# 48V-5V_Buck.net
KiCad netlist of a schematic drawn in Altium Designer
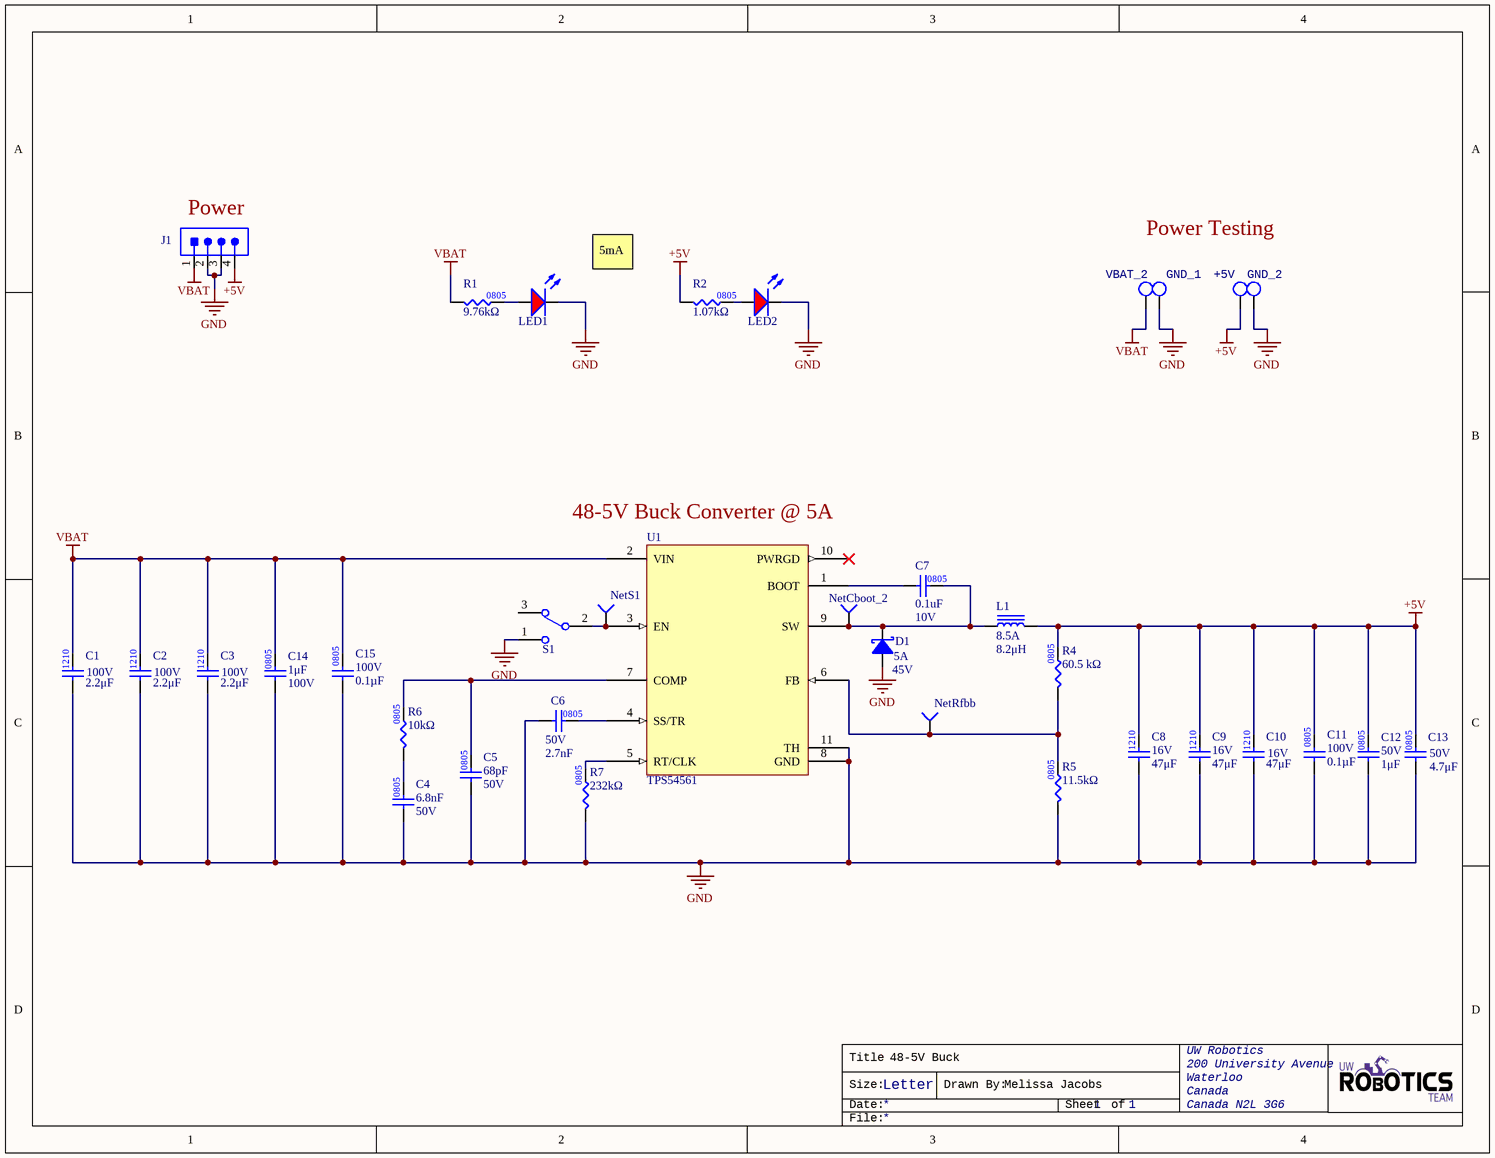
[diagram p0: 48V-5V Buck.SchDoc]

(export (version "E")
  (design (tool "Eeschema 10.0.6"))
  (components
    (comp (ref "+5V")
      (value "TESTPOINT_LOOP")
      (footprint "TESTPOINT_LOOP")
      (description "TESTPOINT THRUHOLE")
      (libsource (lib "UWRT_Schematic_Library_2020") (part "TESTPOINT_LOOP"))
    )
    (comp (ref "C1")
      (value "2.2μF")
      (footprint "CAPC3225X270N")
      (description "CAP CER 2.2UF 100V X7R 1210")
      (fields (field (name "VOLTAGE RATING") "100V") (field (name "Comment") "CAP_2.2uF_100V_1210_1"))
      (libsource (lib "UWRT_Schematic_Library_2020") (part "CAP_2.2uF_100V_1210_1"))
    )
    (comp (ref "C2")
      (value "2.2μF")
      (footprint "CAPC3225X270N")
      (description "CAP CER 2.2UF 100V X7R 1210")
      (fields (field (name "VOLTAGE RATING") "100V") (field (name "Comment") "CAP_2.2uF_100V_1210_1"))
      (libsource (lib "UWRT_Schematic_Library_2020") (part "CAP_2.2uF_100V_1210_1"))
    )
    (comp (ref "C3")
      (value "2.2μF")
      (footprint "CAPC3225X270N")
      (description "CAP CER 2.2UF 100V X7R 1210")
      (fields (field (name "VOLTAGE RATING") "100V") (field (name "Comment") "CAP_2.2uF_100V_1210_1"))
      (libsource (lib "UWRT_Schematic_Library_2020") (part "CAP_2.2uF_100V_1210_1"))
    )
    (comp (ref "C4")
      (value "6.8nF")
      (footprint "CAP0805")
      (description "CAP CER 6800PF 50V C0G/NP0 0805")
      (fields (field (name "VOLTAGE RATING") "50V") (field (name "Comment") "CAP_6.8nF_100V_0805"))
      (libsource (lib "UWRT_Schematic_Library_2020") (part "CAP_6.8nF_100V_0805"))
    )
    (comp (ref "C5")
      (value "68pF")
      (footprint "CAP0805")
      (description "CAP CER 68PF 50V C0G/NP0 0805")
      (fields (field (name "VOLTAGE RATING") "50V") (field (name "Comment") "CAP_68pF_50V_0805"))
      (libsource (lib "UWRT_Schematic_Library_2020") (part "CAP_68pF_50V_0805"))
    )
    (comp (ref "C6")
      (value "2.7nF")
      (footprint "CAP0805")
      (description "CAP CER 2700PF 50V C0G 0805")
      (fields (field (name "VOLTAGE RATING") "50V") (field (name "Comment") "CAP_2.7nF_50V_0805"))
      (libsource (lib "UWRT_Schematic_Library_2020") (part "CAP_2.7nF_50V_0805"))
    )
    (comp (ref "C7")
      (value "0.1uF")
      (footprint "CAP0805")
      (description "CAP CER 0.1uF 10V 0805")
      (fields (field (name "VOLTAGE RATING") "10V") (field (name "Comment") "CAP_0.1uF_10V_0805"))
      (libsource (lib "UWRT_Schematic_Library_2020") (part "CAP_0.1uF_10V_0805"))
    )
    (comp (ref "C8")
      (value "47μF")
      (footprint "CAPC3225X270N")
      (description "CAP CER 47uF 16V X5R 1210")
      (fields (field (name "VOLTAGE RATING") "16V") (field (name "Comment") "CAP_47uF_16V_1210"))
      (libsource (lib "UWRT_Schematic_Library_2020") (part "CAP_47uF_16V_1210"))
    )
    (comp (ref "C9")
      (value "47μF")
      (footprint "CAPC3225X270N")
      (description "CAP CER 47uF 16V X5R 1210")
      (fields (field (name "VOLTAGE RATING") "16V") (field (name "Comment") "CAP_47uF_16V_1210"))
      (libsource (lib "UWRT_Schematic_Library_2020") (part "CAP_47uF_16V_1210"))
    )
    (comp (ref "C10")
      (value "47μF")
      (footprint "CAPC3225X270N")
      (description "CAP CER 47uF 16V X5R 1210")
      (fields (field (name "VOLTAGE RATING") "16V") (field (name "Comment") "CAP_47uF_16V_1210"))
      (libsource (lib "UWRT_Schematic_Library_2020") (part "CAP_47uF_16V_1210"))
    )
    (comp (ref "C11")
      (value "0.1µF")
      (footprint "CAP0805")
      (description "CAP CER 0.1UF 100V X7R 0805")
      (fields (field (name "VOLTAGE RATING") "100V") (field (name "Comment") "CAP_0.1uF_100V_0805"))
      (libsource (lib "UWRT_Schematic_Library_2020") (part "CAP_0.1uF_100V_0805"))
    )
    (comp (ref "C12")
      (value "1μF")
      (footprint "CAP0805")
      (description "CAP CER 1UF 50V X7R 0805")
      (fields
        (field (name "LCSC PART #") "C28323")
        (field (name "VOLTAGE RATING") "50V")
        (field (name "Comment") "CAP_1uF_50V_0805")
      )
      (libsource (lib "UWRT_Schematic_Library_2020") (part "CAP_1uF_50V_0805"))
    )
    (comp (ref "C13")
      (value "4.7μF")
      (footprint "CAP0805")
      (description "CAP CER 4.7UF 50V X5R 0805")
      (fields
        (field (name "LCSC PART #") "C1779")
        (field (name "VOLTAGE RATING") "50V")
        (field (name "Comment") "CAP_4.7uF_50V_0805")
      )
      (libsource (lib "UWRT_Schematic_Library_2020") (part "CAP_4.7uF_50V_0805"))
    )
    (comp (ref "C14")
      (value "1μF")
      (footprint "CAP0805")
      (description "CAP CER 1UF 100V X7S 0805")
      (fields (field (name "VOLTAGE RATING") "100V") (field (name "Comment") "CAP_1uF_100V_0805"))
      (libsource (lib "UWRT_Schematic_Library_2020") (part "CAP_1uF_100V_0805"))
    )
    (comp (ref "C15")
      (value "0.1µF")
      (footprint "CAP0805")
      (description "CAP CER 0.1UF 100V X7R 0805")
      (fields (field (name "VOLTAGE RATING") "100V") (field (name "Comment") "CAP_0.1uF_100V_0805"))
      (libsource (lib "UWRT_Schematic_Library_2020") (part "CAP_0.1uF_100V_0805"))
    )
    (comp (ref "D1")
      (value "DIO_SCHOTTKY_100V_5.5A")
      (footprint "DIO_SCHOTTKY_45V_5A_vF480mV")
      (description "DIODE SCHOTTKY 45V 5A DO214AA")
      (fields (field (name "AVERAGE RECTIFIED CURRENT") "5A") (field (name "VR (MAX)") "45V"))
      (libsource (lib "UWRT_Schematic_Library_2020") (part "DIO_SCHOTTKY_45V_5A"))
    )
    (comp (ref "GND_1")
      (value "TESTPOINT_LOOP")
      (footprint "TESTPOINT_LOOP")
      (description "TESTPOINT THRUHOLE")
      (libsource (lib "UWRT_Schematic_Library_2020") (part "TESTPOINT_LOOP"))
    )
    (comp (ref "GND_2")
      (value "TESTPOINT_LOOP")
      (footprint "TESTPOINT_LOOP")
      (description "TESTPOINT THRUHOLE")
      (libsource (lib "UWRT_Schematic_Library_2020") (part "TESTPOINT_LOOP"))
    )
    (comp (ref "J1")
      (value "CON_2POS_SCREW_TERM")
      (footprint "MPT-04-01-01-L-RA-SD")
      (description "CONN HDR 4POS 5MM R/A SLDR")
      (libsource (lib "UWRT_Schematic_Library_2020") (part "CON_4POS_POWERBLADE_MALE"))
    )
    (comp (ref "L1")
      (value "8.2μH")
      (footprint "IND_8.2uH_8.5A")
      (description "FIXED IND 8.2UH 8.5A 28 MOHM SMD")
      (fields (field (name "CURRENT RATING") "8.5A") (field (name "Comment") "IND_8.2uH_8.5A"))
      (libsource (lib "UWRT_Schematic_Library_2020") (part "IND_8.2uH_8.5A"))
    )
    (comp (ref "LED1")
      (value "LED_RED")
      (footprint "LED_0805_RED")
      (description "LED RED DIFFUSED 0805 SMD")
      (libsource (lib "UWRT_Schematic_Library_2020") (part "LED_RED"))
    )
    (comp (ref "LED2")
      (value "LED_RED")
      (footprint "LED_0805_RED")
      (description "LED RED DIFFUSED 0805 SMD")
      (libsource (lib "UWRT_Schematic_Library_2020") (part "LED_RED"))
    )
    (comp (ref "NetCboot_2")
      (value "TESTPOINT_1MM_CIRCLE")
      (footprint "TESTPOINT_CIRCLE_1MM")
      (description "TESTPOINT 1MM CIRCLE")
      (libsource (lib "UWRT_Schematic_Library_2020") (part "TESTPOINT_1MM_CIRCLE"))
    )
    (comp (ref "NetRfbb")
      (value "TESTPOINT_1MM_CIRCLE")
      (footprint "TESTPOINT_CIRCLE_1MM")
      (description "TESTPOINT 1MM CIRCLE")
      (libsource (lib "UWRT_Schematic_Library_2020") (part "TESTPOINT_1MM_CIRCLE"))
    )
    (comp (ref "NetS1")
      (value "TESTPOINT_1MM_CIRCLE")
      (footprint "TESTPOINT_CIRCLE_1MM")
      (description "TESTPOINT 1MM CIRCLE")
      (libsource (lib "UWRT_Schematic_Library_2020") (part "TESTPOINT_1MM_CIRCLE"))
    )
    (comp (ref "R1")
      (value "9.76kΩ")
      (footprint "RES0805")
      (description "RES 9.76K OHM 1% 1/8W 0805")
      (fields (field (name "Comment") "RES_9.76kΩ_0805_1%"))
      (libsource (lib "UWRT_Schematic_Library_2020") (part "RES_9.76kΩ_0805_1%"))
    )
    (comp (ref "R2")
      (value "1.07kΩ")
      (footprint "RES0805")
      (description "RES 1K OHM 1% 1/8W 0805")
      (fields (field (name "Comment") "RES_1kΩ_0805_1%"))
      (libsource (lib "UWRT_Schematic_Library_2020") (part "RES_1kΩ_0805_1%"))
    )
    (comp (ref "R4")
      (value "60.5 kΩ")
      (footprint "RES0805")
      (description "RES 60.5 kOHM 63 mW 0805")
      (fields (field (name "Comment") "RES_60.4kΩ_0805_1%"))
      (libsource (lib "UWRT_Schematic_Library_2020") (part "RES_60.4kΩ_0805_1%"))
    )
    (comp (ref "R5")
      (value "11.5kΩ")
      (footprint "RES0805")
      (description "RES 11.5K OHM 0.1% 1/10W 0805")
      (fields (field (name "Comment") "RES_11.5kΩ_0805_0.1%"))
      (libsource (lib "UWRT_Schematic_Library_2020") (part "RES_11.5kΩ_0805_0.1%"))
    )
    (comp (ref "R6")
      (value "10kΩ")
      (footprint "RES0805")
      (description "RES 10K OHM 5% 1/8W 0805")
      (fields (field (name "LCSC PART #") "C17414") (field (name "Comment") "RES_10kΩ_0805_5%"))
      (libsource (lib "UWRT_Schematic_Library_2020") (part "RES_10kΩ_0805_5%"))
    )
    (comp (ref "R7")
      (value "232kΩ")
      (footprint "RES0805")
      (description "RES 232K OHM 1% 1/8W 0805")
      (fields (field (name "LCSC PART #") "0") (field (name "Comment") "RES_232kΩ_0805_1%"))
      (libsource (lib "UWRT_Schematic_Library_2020") (part "RES_232kΩ_0805_1%"))
    )
    (comp (ref "S1")
      (value "SW_SLIDE_TOGGLE")
      (footprint "UWRT_Footprint_Library_2020:SW_SLIDE_TOGGLE")
      (description "SWITCH SLIDE SPDT 200MA 30V")
      (libsource (lib "UWRT_Schematic_Library_2020") (part "SW_SLIDE_TOGGLE"))
    )
    (comp (ref "U1")
      (value "TPS54561")
      (footprint "BUCK_TPS54561DPRR")
      (description "Buck Switching Regulator IC Positive Adjustable 0.8V 1 Output 5A 10-WDFN Exposed Pad")
      (libsource (lib "UWRT_Schematic_Library_2020") (part "TPS54561"))
    )
    (comp (ref "VBAT_2")
      (value "TESTPOINT_LOOP")
      (footprint "TESTPOINT_LOOP")
      (description "TESTPOINT THRUHOLE")
      (libsource (lib "UWRT_Schematic_Library_2020") (part "TESTPOINT_LOOP"))
    )
  )
  (nets
    (net (code "1") (name "+5V") (class "Default")
      (node (ref "+5V") (pin "1") (pintype "passive"))
      (node (ref "C10") (pin "2") (pinfunction "2_2") (pintype "passive"))
      (node (ref "C11") (pin "2") (pinfunction "2_2") (pintype "passive"))
      (node (ref "C12") (pin "2") (pinfunction "2_2") (pintype "passive"))
      (node (ref "C13") (pin "2") (pinfunction "2_2") (pintype "passive"))
      (node (ref "C8") (pin "2") (pinfunction "2_2") (pintype "passive"))
      (node (ref "C9") (pin "2") (pinfunction "2_2") (pintype "passive"))
      (node (ref "J1") (pin "4") (pinfunction "2_4") (pintype "passive"))
      (node (ref "L1") (pin "2") (pinfunction "2_2") (pintype "passive"))
      (node (ref "R2") (pin "1") (pinfunction "1_1") (pintype "passive"))
      (node (ref "R4") (pin "2") (pinfunction "2_2") (pintype "passive"))
    )
    (net (code "2") (name "GND") (class "Default")
      (node (ref "C1") (pin "1") (pinfunction "1_1") (pintype "passive"))
      (node (ref "C10") (pin "1") (pinfunction "1_1") (pintype "passive"))
      (node (ref "C11") (pin "1") (pinfunction "1_1") (pintype "passive"))
      (node (ref "C12") (pin "1") (pinfunction "1_1") (pintype "passive"))
      (node (ref "C13") (pin "1") (pinfunction "1_1") (pintype "passive"))
      (node (ref "C14") (pin "1") (pinfunction "1_1") (pintype "passive"))
      (node (ref "C15") (pin "1") (pinfunction "1_1") (pintype "passive"))
      (node (ref "C2") (pin "1") (pinfunction "1_1") (pintype "passive"))
      (node (ref "C3") (pin "1") (pinfunction "1_1") (pintype "passive"))
      (node (ref "C4") (pin "1") (pinfunction "1_1") (pintype "passive"))
      (node (ref "C5") (pin "1") (pinfunction "1_1") (pintype "passive"))
      (node (ref "C6") (pin "1") (pinfunction "1_1") (pintype "passive"))
      (node (ref "C8") (pin "1") (pinfunction "1_1") (pintype "passive"))
      (node (ref "C9") (pin "1") (pinfunction "1_1") (pintype "passive"))
      (node (ref "D1") (pin "1") (pinfunction "Anode_1") (pintype "passive"))
      (node (ref "GND_1") (pin "1") (pintype "passive"))
      (node (ref "GND_2") (pin "1") (pintype "passive"))
      (node (ref "J1") (pin "2") (pinfunction "2_2") (pintype "passive"))
      (node (ref "J1") (pin "3") (pinfunction "1_3") (pintype "passive"))
      (node (ref "LED1") (pin "2") (pinfunction "K_2") (pintype "passive"))
      (node (ref "LED2") (pin "2") (pinfunction "K_2") (pintype "passive"))
      (node (ref "R5") (pin "1") (pinfunction "1_1") (pintype "passive"))
      (node (ref "R7") (pin "1") (pinfunction "1_1") (pintype "passive"))
      (node (ref "S1") (pin "1") (pinfunction "1_1") (pintype "passive"))
      (node (ref "U1") (pin "11") (pinfunction "TH_11") (pintype "power_in"))
      (node (ref "U1") (pin "8") (pinfunction "GND_8") (pintype "power_in"))
    )
    (net (code "3") (name "Net-(C4-Pad2)") (class "Default")
      (node (ref "C4") (pin "2") (pinfunction "2_2") (pintype "passive"))
      (node (ref "R6") (pin "1") (pinfunction "1_1") (pintype "passive"))
    )
    (net (code "4") (name "Net-(D1-Cathode)") (class "Default")
      (node (ref "C7") (pin "2") (pinfunction "2_2") (pintype "passive"))
      (node (ref "D1") (pin "2") (pinfunction "Cathode_2") (pintype "passive"))
      (node (ref "L1") (pin "1") (pinfunction "1_1") (pintype "passive"))
      (node (ref "NetCboot_2") (pin "1") (pinfunction "=value_1") (pintype "passive"))
      (node (ref "U1") (pin "9") (pinfunction "SW_9") (pintype "power_in"))
    )
    (net (code "5") (name "Net-(LED1-A)") (class "Default")
      (node (ref "LED1") (pin "1") (pinfunction "A_1") (pintype "passive"))
      (node (ref "R1") (pin "2") (pinfunction "2_2") (pintype "passive"))
    )
    (net (code "6") (name "Net-(LED2-A)") (class "Default")
      (node (ref "LED2") (pin "1") (pinfunction "A_1") (pintype "passive"))
      (node (ref "R2") (pin "2") (pinfunction "2_2") (pintype "passive"))
    )
    (net (code "7") (name "Net-(NetRfbb-=value)") (class "Default")
      (node (ref "NetRfbb") (pin "1") (pinfunction "=value_1") (pintype "passive"))
      (node (ref "R4") (pin "1") (pinfunction "1_1") (pintype "passive"))
      (node (ref "R5") (pin "2") (pinfunction "2_2") (pintype "passive"))
      (node (ref "U1") (pin "6") (pinfunction "FB_6") (pintype "input"))
    )
    (net (code "8") (name "Net-(NetS1-=value)") (class "Default")
      (node (ref "NetS1") (pin "1") (pinfunction "=value_1") (pintype "passive"))
      (node (ref "S1") (pin "2") (pinfunction "2_2") (pintype "passive"))
      (node (ref "U1") (pin "3") (pinfunction "EN_3") (pintype "input"))
    )
    (net (code "9") (name "Net-(U1-BOOT)") (class "Default")
      (node (ref "C7") (pin "1") (pinfunction "1_1") (pintype "passive"))
      (node (ref "U1") (pin "1") (pinfunction "BOOT_1") (pintype "power_in"))
    )
    (net (code "10") (name "Net-(U1-COMP)") (class "Default")
      (node (ref "C5") (pin "2") (pinfunction "2_2") (pintype "passive"))
      (node (ref "R6") (pin "2") (pinfunction "2_2") (pintype "passive"))
      (node (ref "U1") (pin "7") (pinfunction "COMP_7") (pintype "power_in"))
    )
    (net (code "11") (name "Net-(U1-RT{slash}CLK)") (class "Default")
      (node (ref "R7") (pin "2") (pinfunction "2_2") (pintype "passive"))
      (node (ref "U1") (pin "5") (pinfunction "RT/CLK_5") (pintype "input"))
    )
    (net (code "12") (name "Net-(U1-SS{slash}TR)") (class "Default")
      (node (ref "C6") (pin "2") (pinfunction "2_2") (pintype "passive"))
      (node (ref "U1") (pin "4") (pinfunction "SS/TR_4") (pintype "input"))
    )
    (net (code "13") (name "VBAT") (class "Default")
      (node (ref "C1") (pin "2") (pinfunction "2_2") (pintype "passive"))
      (node (ref "C14") (pin "2") (pinfunction "2_2") (pintype "passive"))
      (node (ref "C15") (pin "2") (pinfunction "2_2") (pintype "passive"))
      (node (ref "C2") (pin "2") (pinfunction "2_2") (pintype "passive"))
      (node (ref "C3") (pin "2") (pinfunction "2_2") (pintype "passive"))
      (node (ref "J1") (pin "1") (pinfunction "1_1") (pintype "passive"))
      (node (ref "R1") (pin "1") (pinfunction "1_1") (pintype "passive"))
      (node (ref "U1") (pin "2") (pinfunction "VIN_2") (pintype "power_in"))
      (node (ref "VBAT_2") (pin "1") (pintype "passive"))
    )
    (net (code "14") (name "unconnected-(S1-Pad3)") (class "Default")
      (node (ref "S1") (pin "3") (pinfunction "3_3") (pintype "passive"))
    )
    (net (code "15") (name "unconnected-(U1-PWRGD-Pad10)") (class "Default")
      (node (ref "U1") (pin "10") (pinfunction "PWRGD_10") (pintype "output+no_connect"))
    )
  )
)
